# CNY70_dev.net
KiCad netlist of a schematic drawn in EAGLE
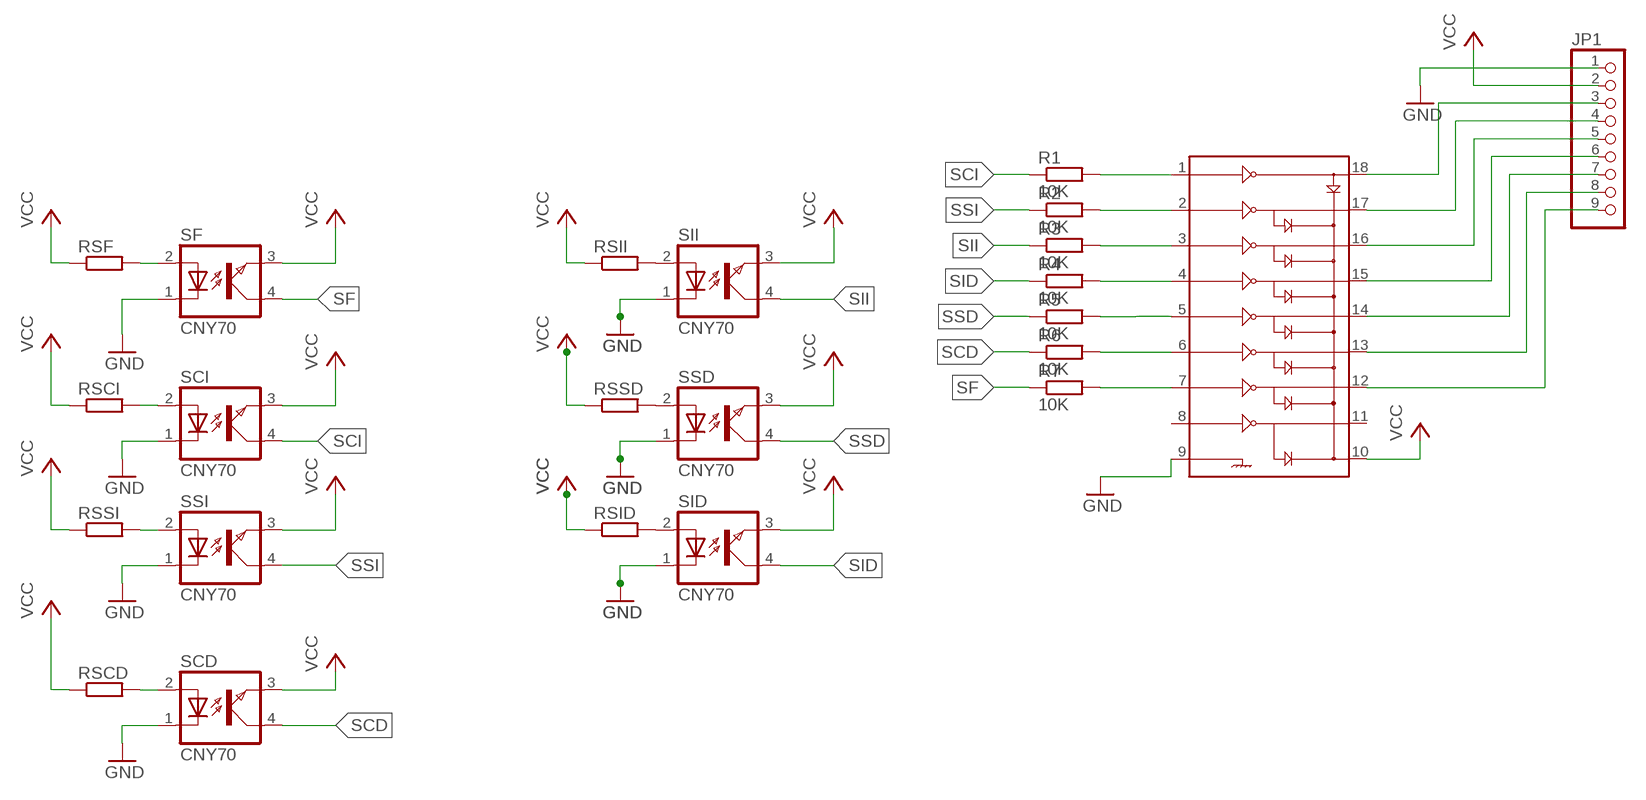
[diagram p0: schematic, sheet 1]

(export (version "E")
  (design (tool "Eeschema 10.0.6"))
  (components
    (comp (ref "JP1")
      (value "PINHD-1X9/90")
      (footprint "eagle-import:1X09_90")
      (libsource (lib "eagle-import") (part "PINHD-1X9/90"))
    )
    (comp (ref "R1")
      (value "10K")
      (footprint "eagle-import:R1206")
      (libsource (lib "eagle-import") (part "R-EU_R1206"))
    )
    (comp (ref "R2")
      (value "10K")
      (footprint "eagle-import:R1206")
      (libsource (lib "eagle-import") (part "R-EU_R1206"))
    )
    (comp (ref "R3")
      (value "10K")
      (footprint "eagle-import:R1206")
      (libsource (lib "eagle-import") (part "R-EU_R1206"))
    )
    (comp (ref "R4")
      (value "10K")
      (footprint "eagle-import:R1206")
      (libsource (lib "eagle-import") (part "R-EU_R1206"))
    )
    (comp (ref "R5")
      (value "10K")
      (footprint "eagle-import:R1206")
      (libsource (lib "eagle-import") (part "R-EU_R1206"))
    )
    (comp (ref "R6")
      (value "10K")
      (footprint "eagle-import:R1206")
      (libsource (lib "eagle-import") (part "R-EU_R1206"))
    )
    (comp (ref "R7")
      (value "10K")
      (footprint "eagle-import:R1206")
      (libsource (lib "eagle-import") (part "R-EU_R1206"))
    )
    (comp (ref "RSCD")
      (value "R-EU_R1206")
      (footprint "eagle-import:R1206")
      (libsource (lib "eagle-import") (part "R-EU_R1206"))
    )
    (comp (ref "RSCI")
      (value "R-EU_R1206")
      (footprint "eagle-import:R1206")
      (libsource (lib "eagle-import") (part "R-EU_R1206"))
    )
    (comp (ref "RSF")
      (value "R-EU_R1206")
      (footprint "eagle-import:R1206")
      (libsource (lib "eagle-import") (part "R-EU_R1206"))
    )
    (comp (ref "RSID")
      (value "R-EU_R1206")
      (footprint "eagle-import:R1206")
      (libsource (lib "eagle-import") (part "R-EU_R1206"))
    )
    (comp (ref "RSII")
      (value "R-EU_R1206")
      (footprint "eagle-import:R1206")
      (libsource (lib "eagle-import") (part "R-EU_R1206"))
    )
    (comp (ref "RSSD")
      (value "R-EU_R1206")
      (footprint "eagle-import:R1206")
      (libsource (lib "eagle-import") (part "R-EU_R1206"))
    )
    (comp (ref "RSSI")
      (value "R-EU_R1206")
      (footprint "eagle-import:R1206")
      (libsource (lib "eagle-import") (part "R-EU_R1206"))
    )
    (comp (ref "SCD")
      (value "CNY70")
      (footprint "eagle-import:CNY70")
      (libsource (lib "eagle-import") (part "CNY70"))
    )
    (comp (ref "SCI")
      (value "CNY70")
      (footprint "eagle-import:CNY70")
      (libsource (lib "eagle-import") (part "CNY70"))
    )
    (comp (ref "SF")
      (value "CNY70")
      (footprint "eagle-import:CNY70")
      (libsource (lib "eagle-import") (part "CNY70"))
    )
    (comp (ref "SID")
      (value "CNY70")
      (footprint "eagle-import:CNY70")
      (libsource (lib "eagle-import") (part "CNY70"))
    )
    (comp (ref "SII")
      (value "CNY70")
      (footprint "eagle-import:CNY70")
      (libsource (lib "eagle-import") (part "CNY70"))
    )
    (comp (ref "SSD")
      (value "CNY70")
      (footprint "eagle-import:CNY70")
      (libsource (lib "eagle-import") (part "CNY70"))
    )
    (comp (ref "SSI")
      (value "CNY70")
      (footprint "eagle-import:CNY70")
      (libsource (lib "eagle-import") (part "CNY70"))
    )
    (comp (ref "ULN1")
      (value "ULN2803")
      (footprint "eagle-import:DIL18")
      (libsource (lib "eagle-import") (part "ULN2803"))
    )
  )
  (nets
    (net (code "1") (name "GND") (class "Default")
      (node (ref "JP1") (pin "1") (pinfunction "1_1") (pintype "passive"))
      (node (ref "SCD") (pin "1") (pinfunction "1_1") (pintype "passive"))
      (node (ref "SCI") (pin "1") (pinfunction "1_1") (pintype "passive"))
      (node (ref "SF") (pin "1") (pinfunction "1_1") (pintype "passive"))
      (node (ref "SID") (pin "1") (pinfunction "1_1") (pintype "passive"))
      (node (ref "SII") (pin "1") (pinfunction "1_1") (pintype "passive"))
      (node (ref "SSD") (pin "1") (pinfunction "1_1") (pintype "passive"))
      (node (ref "SSI") (pin "1") (pinfunction "1_1") (pintype "passive"))
      (node (ref "ULN1") (pin "9") (pinfunction "9_9") (pintype "bidirectional"))
    )
    (net (code "2") (name "Net-(JP1-Pad3)") (class "Default")
      (node (ref "JP1") (pin "3") (pinfunction "3_3") (pintype "passive"))
      (node (ref "ULN1") (pin "18") (pinfunction "18_18") (pintype "bidirectional"))
    )
    (net (code "3") (name "Net-(JP1-Pad4)") (class "Default")
      (node (ref "JP1") (pin "4") (pinfunction "4_4") (pintype "passive"))
      (node (ref "ULN1") (pin "17") (pinfunction "17_17") (pintype "bidirectional"))
    )
    (net (code "4") (name "Net-(JP1-Pad5)") (class "Default")
      (node (ref "JP1") (pin "5") (pinfunction "5_5") (pintype "passive"))
      (node (ref "ULN1") (pin "16") (pinfunction "16_16") (pintype "bidirectional"))
    )
    (net (code "5") (name "Net-(JP1-Pad6)") (class "Default")
      (node (ref "JP1") (pin "6") (pinfunction "6_6") (pintype "passive"))
      (node (ref "ULN1") (pin "15") (pinfunction "15_15") (pintype "bidirectional"))
    )
    (net (code "6") (name "Net-(JP1-Pad7)") (class "Default")
      (node (ref "JP1") (pin "7") (pinfunction "7_7") (pintype "passive"))
      (node (ref "ULN1") (pin "14") (pinfunction "14_14") (pintype "bidirectional"))
    )
    (net (code "7") (name "Net-(JP1-Pad8)") (class "Default")
      (node (ref "JP1") (pin "8") (pinfunction "8_8") (pintype "passive"))
      (node (ref "ULN1") (pin "13") (pinfunction "13_13") (pintype "bidirectional"))
    )
    (net (code "8") (name "Net-(JP1-Pad9)") (class "Default")
      (node (ref "JP1") (pin "9") (pinfunction "9_9") (pintype "passive"))
      (node (ref "ULN1") (pin "12") (pinfunction "12_12") (pintype "bidirectional"))
    )
    (net (code "9") (name "Net-(R1-Pad2)") (class "Default")
      (node (ref "R1") (pin "2") (pinfunction "2_2") (pintype "passive"))
      (node (ref "ULN1") (pin "1") (pinfunction "1_1") (pintype "bidirectional"))
    )
    (net (code "10") (name "Net-(R2-Pad2)") (class "Default")
      (node (ref "R2") (pin "2") (pinfunction "2_2") (pintype "passive"))
      (node (ref "ULN1") (pin "2") (pinfunction "2_2") (pintype "bidirectional"))
    )
    (net (code "11") (name "Net-(R3-Pad2)") (class "Default")
      (node (ref "R3") (pin "2") (pinfunction "2_2") (pintype "passive"))
      (node (ref "ULN1") (pin "3") (pinfunction "3_3") (pintype "bidirectional"))
    )
    (net (code "12") (name "Net-(R4-Pad2)") (class "Default")
      (node (ref "R4") (pin "2") (pinfunction "2_2") (pintype "passive"))
      (node (ref "ULN1") (pin "4") (pinfunction "4_4") (pintype "bidirectional"))
    )
    (net (code "13") (name "Net-(R5-Pad2)") (class "Default")
      (node (ref "R5") (pin "2") (pinfunction "2_2") (pintype "passive"))
      (node (ref "ULN1") (pin "5") (pinfunction "5_5") (pintype "bidirectional"))
    )
    (net (code "14") (name "Net-(R6-Pad2)") (class "Default")
      (node (ref "R6") (pin "2") (pinfunction "2_2") (pintype "passive"))
      (node (ref "ULN1") (pin "6") (pinfunction "6_6") (pintype "bidirectional"))
    )
    (net (code "15") (name "Net-(R7-Pad2)") (class "Default")
      (node (ref "R7") (pin "2") (pinfunction "2_2") (pintype "passive"))
      (node (ref "ULN1") (pin "7") (pinfunction "7_7") (pintype "bidirectional"))
    )
    (net (code "16") (name "Net-(RSCD-Pad2)") (class "Default")
      (node (ref "RSCD") (pin "2") (pinfunction "2_2") (pintype "passive"))
      (node (ref "SCD") (pin "2") (pinfunction "2_2") (pintype "passive"))
    )
    (net (code "17") (name "Net-(RSCI-Pad2)") (class "Default")
      (node (ref "RSCI") (pin "2") (pinfunction "2_2") (pintype "passive"))
      (node (ref "SCI") (pin "2") (pinfunction "2_2") (pintype "passive"))
    )
    (net (code "18") (name "Net-(RSF-Pad2)") (class "Default")
      (node (ref "RSF") (pin "2") (pinfunction "2_2") (pintype "passive"))
      (node (ref "SF") (pin "2") (pinfunction "2_2") (pintype "passive"))
    )
    (net (code "19") (name "Net-(RSID-Pad2)") (class "Default")
      (node (ref "RSID") (pin "2") (pinfunction "2_2") (pintype "passive"))
      (node (ref "SID") (pin "2") (pinfunction "2_2") (pintype "passive"))
    )
    (net (code "20") (name "Net-(RSII-Pad2)") (class "Default")
      (node (ref "RSII") (pin "2") (pinfunction "2_2") (pintype "passive"))
      (node (ref "SII") (pin "2") (pinfunction "2_2") (pintype "passive"))
    )
    (net (code "21") (name "Net-(RSSD-Pad2)") (class "Default")
      (node (ref "RSSD") (pin "2") (pinfunction "2_2") (pintype "passive"))
      (node (ref "SSD") (pin "2") (pinfunction "2_2") (pintype "passive"))
    )
    (net (code "22") (name "Net-(RSSI-Pad2)") (class "Default")
      (node (ref "RSSI") (pin "2") (pinfunction "2_2") (pintype "passive"))
      (node (ref "SSI") (pin "2") (pinfunction "2_2") (pintype "passive"))
    )
    (net (code "23") (name "SCD") (class "Default")
      (node (ref "R6") (pin "1") (pinfunction "1_1") (pintype "passive"))
      (node (ref "SCD") (pin "4") (pinfunction "4_4") (pintype "passive"))
    )
    (net (code "24") (name "SCI") (class "Default")
      (node (ref "R1") (pin "1") (pinfunction "1_1") (pintype "passive"))
      (node (ref "SCI") (pin "4") (pinfunction "4_4") (pintype "passive"))
    )
    (net (code "25") (name "SF") (class "Default")
      (node (ref "R7") (pin "1") (pinfunction "1_1") (pintype "passive"))
      (node (ref "SF") (pin "4") (pinfunction "4_4") (pintype "passive"))
    )
    (net (code "26") (name "SID") (class "Default")
      (node (ref "R4") (pin "1") (pinfunction "1_1") (pintype "passive"))
      (node (ref "SID") (pin "4") (pinfunction "4_4") (pintype "passive"))
    )
    (net (code "27") (name "SII") (class "Default")
      (node (ref "R3") (pin "1") (pinfunction "1_1") (pintype "passive"))
      (node (ref "SII") (pin "4") (pinfunction "4_4") (pintype "passive"))
    )
    (net (code "28") (name "SSD") (class "Default")
      (node (ref "R5") (pin "1") (pinfunction "1_1") (pintype "passive"))
      (node (ref "SSD") (pin "4") (pinfunction "4_4") (pintype "passive"))
    )
    (net (code "29") (name "SSI") (class "Default")
      (node (ref "R2") (pin "1") (pinfunction "1_1") (pintype "passive"))
      (node (ref "SSI") (pin "4") (pinfunction "4_4") (pintype "passive"))
    )
    (net (code "30") (name "VCC") (class "Default")
      (node (ref "JP1") (pin "2") (pinfunction "2_2") (pintype "passive"))
      (node (ref "RSCD") (pin "1") (pinfunction "1_1") (pintype "passive"))
      (node (ref "RSCI") (pin "1") (pinfunction "1_1") (pintype "passive"))
      (node (ref "RSF") (pin "1") (pinfunction "1_1") (pintype "passive"))
      (node (ref "RSID") (pin "1") (pinfunction "1_1") (pintype "passive"))
      (node (ref "RSII") (pin "1") (pinfunction "1_1") (pintype "passive"))
      (node (ref "RSSD") (pin "1") (pinfunction "1_1") (pintype "passive"))
      (node (ref "RSSI") (pin "1") (pinfunction "1_1") (pintype "passive"))
      (node (ref "SCD") (pin "3") (pinfunction "3_3") (pintype "passive"))
      (node (ref "SCI") (pin "3") (pinfunction "3_3") (pintype "passive"))
      (node (ref "SF") (pin "3") (pinfunction "3_3") (pintype "passive"))
      (node (ref "SID") (pin "3") (pinfunction "3_3") (pintype "passive"))
      (node (ref "SII") (pin "3") (pinfunction "3_3") (pintype "passive"))
      (node (ref "SSD") (pin "3") (pinfunction "3_3") (pintype "passive"))
      (node (ref "SSI") (pin "3") (pinfunction "3_3") (pintype "passive"))
      (node (ref "ULN1") (pin "10") (pinfunction "10_10") (pintype "bidirectional"))
    )
    (net (code "31") (name "unconnected-(ULN1-Pad8)") (class "Default")
      (node (ref "ULN1") (pin "8") (pinfunction "8_8") (pintype "bidirectional"))
    )
    (net (code "32") (name "unconnected-(ULN1-Pad11)") (class "Default")
      (node (ref "ULN1") (pin "11") (pinfunction "11_11") (pintype "bidirectional"))
    )
  )
)
